# Digital_Output_C.net
KiCad netlist of a schematic drawn in EAGLE
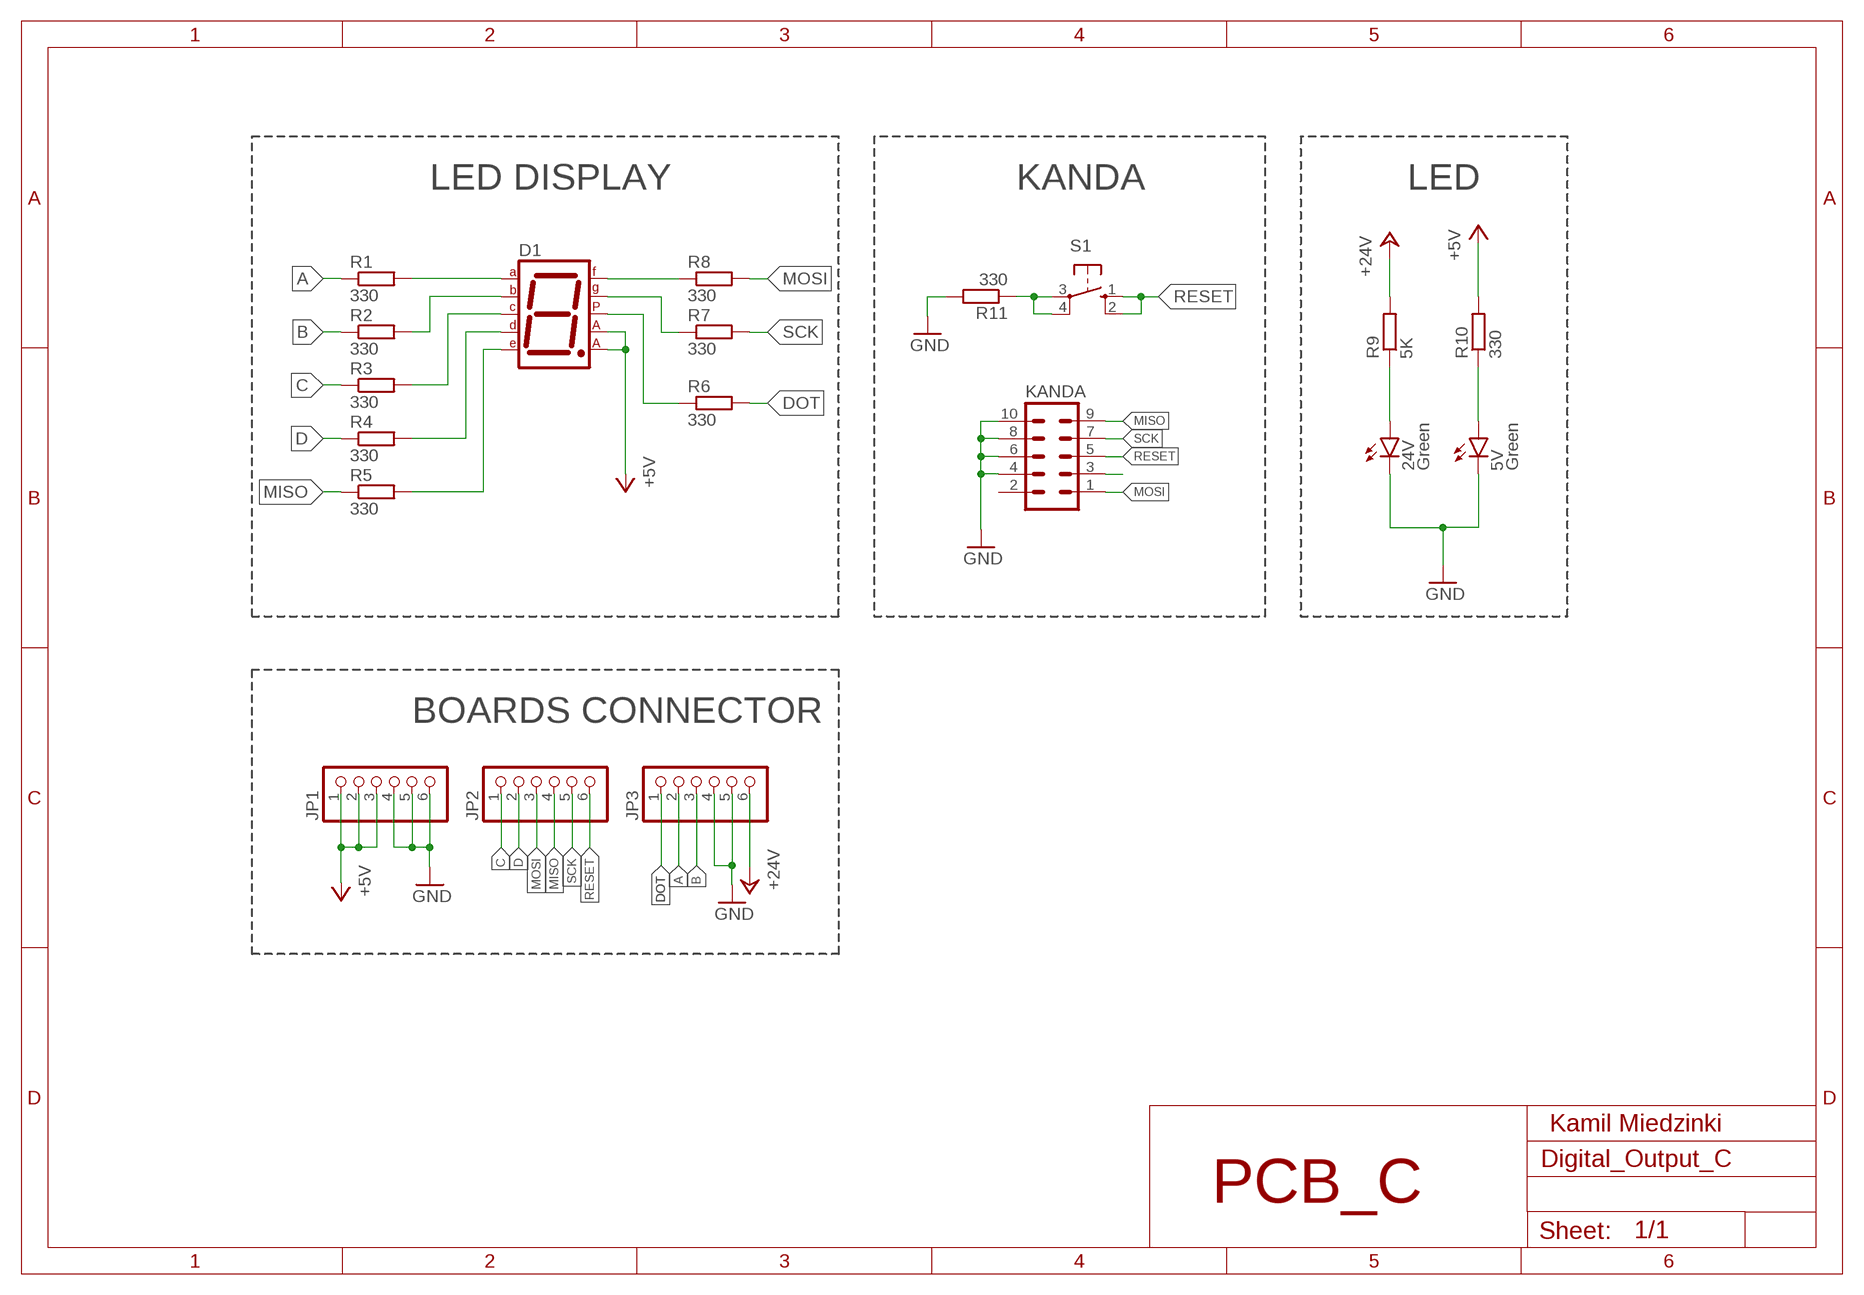
[diagram p0: schematic, sheet 1]

(export (version "E")
  (design (tool "Eeschema 10.0.6"))
  (components
    (comp (ref "5V")
      (value "Green")
      (footprint "eagle-import:LED5MM")
      (libsource (lib "eagle-import") (part "LED5MM"))
    )
    (comp (ref "24V")
      (value "Green")
      (footprint "eagle-import:LED5MM")
      (libsource (lib "eagle-import") (part "LED5MM"))
    )
    (comp (ref "D1")
      (value "7SEG-CA")
      (footprint "eagle-import:7SEG-13")
      (libsource (lib "eagle-import") (part "7SEG-CA"))
    )
    (comp (ref "JP1")
      (value "PINHD-1X6\"")
      (footprint "eagle-import:1X06H")
      (libsource (lib "eagle-import") (part "PINHD-1X6{dblquote}"))
    )
    (comp (ref "JP2")
      (value "PINHD-1X6\"")
      (footprint "eagle-import:1X06H")
      (libsource (lib "eagle-import") (part "PINHD-1X6{dblquote}"))
    )
    (comp (ref "JP3")
      (value "PINHD-1X6\"")
      (footprint "eagle-import:1X06H")
      (libsource (lib "eagle-import") (part "PINHD-1X6{dblquote}"))
    )
    (comp (ref "KANDA")
      (value "ML10")
      (footprint "eagle-import:ML10")
      (libsource (lib "eagle-import") (part "ML10"))
    )
    (comp (ref "R1")
      (value "330")
      (footprint "eagle-import:R0805")
      (libsource (lib "eagle-import") (part "R-EU_R0805"))
    )
    (comp (ref "R2")
      (value "330")
      (footprint "eagle-import:R0805")
      (libsource (lib "eagle-import") (part "R-EU_R0805"))
    )
    (comp (ref "R3")
      (value "330")
      (footprint "eagle-import:R0805")
      (libsource (lib "eagle-import") (part "R-EU_R0805"))
    )
    (comp (ref "R4")
      (value "330")
      (footprint "eagle-import:R0805")
      (libsource (lib "eagle-import") (part "R-EU_R0805"))
    )
    (comp (ref "R5")
      (value "330")
      (footprint "eagle-import:R0805")
      (libsource (lib "eagle-import") (part "R-EU_R0805"))
    )
    (comp (ref "R6")
      (value "330")
      (footprint "eagle-import:R0805")
      (libsource (lib "eagle-import") (part "R-EU_R0805"))
    )
    (comp (ref "R7")
      (value "330")
      (footprint "eagle-import:R0805")
      (libsource (lib "eagle-import") (part "R-EU_R0805"))
    )
    (comp (ref "R8")
      (value "330")
      (footprint "eagle-import:R0805")
      (libsource (lib "eagle-import") (part "R-EU_R0805"))
    )
    (comp (ref "R9")
      (value "5K")
      (footprint "eagle-import:0207_7")
      (libsource (lib "eagle-import") (part "R-EU_0207/7"))
    )
    (comp (ref "R10")
      (value "330")
      (footprint "eagle-import:0207_7")
      (libsource (lib "eagle-import") (part "R-EU_0207/7"))
    )
    (comp (ref "R11")
      (value "330")
      (footprint "eagle-import:R0805")
      (libsource (lib "eagle-import") (part "R-EU_R0805"))
    )
    (comp (ref "S1")
      (value "10-XX")
      (footprint "eagle-import:B3F-10XX")
      (fields (field (name "MPN") "B3F-1000"))
      (libsource (lib "eagle-import") (part "10-XX"))
    )
  )
  (nets
    (net (code "1") (name "+5V") (class "Default")
      (node (ref "D1") (pin "3") (pinfunction "CA1_3") (pintype "passive"))
      (node (ref "D1") (pin "8") (pinfunction "CA2_8") (pintype "passive"))
      (node (ref "JP1") (pin "1") (pinfunction "1_1") (pintype "passive"))
      (node (ref "JP1") (pin "2") (pinfunction "2_2") (pintype "passive"))
      (node (ref "JP1") (pin "3") (pinfunction "3_3") (pintype "passive"))
      (node (ref "R10") (pin "2") (pinfunction "2_2") (pintype "passive"))
    )
    (net (code "2") (name "+24V") (class "Default")
      (node (ref "JP3") (pin "6") (pinfunction "6_6") (pintype "passive"))
      (node (ref "R9") (pin "2") (pinfunction "2_2") (pintype "passive"))
    )
    (net (code "3") (name "A") (class "Default")
      (node (ref "JP3") (pin "2") (pinfunction "2_2") (pintype "passive"))
      (node (ref "R1") (pin "1") (pinfunction "1_1") (pintype "passive"))
    )
    (net (code "4") (name "B") (class "Default")
      (node (ref "JP3") (pin "3") (pinfunction "3_3") (pintype "passive"))
      (node (ref "R2") (pin "1") (pinfunction "1_1") (pintype "passive"))
    )
    (net (code "5") (name "C") (class "Default")
      (node (ref "JP2") (pin "1") (pinfunction "1_1") (pintype "passive"))
      (node (ref "R3") (pin "1") (pinfunction "1_1") (pintype "passive"))
    )
    (net (code "6") (name "D") (class "Default")
      (node (ref "JP2") (pin "2") (pinfunction "2_2") (pintype "passive"))
      (node (ref "R4") (pin "1") (pinfunction "1_1") (pintype "passive"))
    )
    (net (code "7") (name "DOT") (class "Default")
      (node (ref "JP3") (pin "1") (pinfunction "1_1") (pintype "passive"))
      (node (ref "R6") (pin "2") (pinfunction "2_2") (pintype "passive"))
    )
    (net (code "8") (name "GND") (class "Default")
      (node (ref "24V") (pin "K") (pinfunction "C_K") (pintype "passive"))
      (node (ref "5V") (pin "K") (pinfunction "C_K") (pintype "passive"))
      (node (ref "JP1") (pin "4") (pinfunction "4_4") (pintype "passive"))
      (node (ref "JP1") (pin "5") (pinfunction "5_5") (pintype "passive"))
      (node (ref "JP1") (pin "6") (pinfunction "6_6") (pintype "passive"))
      (node (ref "JP3") (pin "4") (pinfunction "4_4") (pintype "passive"))
      (node (ref "JP3") (pin "5") (pinfunction "5_5") (pintype "passive"))
      (node (ref "KANDA") (pin "10") (pinfunction "10_10") (pintype "passive"))
      (node (ref "KANDA") (pin "4") (pinfunction "4_4") (pintype "passive"))
      (node (ref "KANDA") (pin "6") (pinfunction "6_6") (pintype "passive"))
      (node (ref "KANDA") (pin "8") (pinfunction "8_8") (pintype "passive"))
      (node (ref "R11") (pin "2") (pinfunction "2_2") (pintype "passive"))
    )
    (net (code "9") (name "MISO") (class "Default")
      (node (ref "JP2") (pin "4") (pinfunction "4_4") (pintype "passive"))
      (node (ref "KANDA") (pin "9") (pinfunction "9_9") (pintype "passive"))
      (node (ref "R5") (pin "1") (pinfunction "1_1") (pintype "passive"))
    )
    (net (code "10") (name "MOSI") (class "Default")
      (node (ref "JP2") (pin "3") (pinfunction "3_3") (pintype "passive"))
      (node (ref "KANDA") (pin "1") (pinfunction "1_1") (pintype "passive"))
      (node (ref "R8") (pin "2") (pinfunction "2_2") (pintype "passive"))
    )
    (net (code "11") (name "Net-(5V-PadA)") (class "Default")
      (node (ref "5V") (pin "A") (pinfunction "A_A") (pintype "passive"))
      (node (ref "R10") (pin "1") (pinfunction "1_1") (pintype "passive"))
    )
    (net (code "12") (name "Net-(24V-PadA)") (class "Default")
      (node (ref "24V") (pin "A") (pinfunction "A_A") (pintype "passive"))
      (node (ref "R9") (pin "1") (pinfunction "1_1") (pintype "passive"))
    )
    (net (code "13") (name "Net-(D1-A)") (class "Default")
      (node (ref "D1") (pin "7") (pinfunction "A_7") (pintype "passive"))
      (node (ref "R1") (pin "2") (pinfunction "2_2") (pintype "passive"))
    )
    (net (code "14") (name "Net-(D1-B)") (class "Default")
      (node (ref "D1") (pin "6") (pinfunction "B_6") (pintype "passive"))
      (node (ref "R2") (pin "2") (pinfunction "2_2") (pintype "passive"))
    )
    (net (code "15") (name "Net-(D1-C)") (class "Default")
      (node (ref "D1") (pin "4") (pinfunction "C_4") (pintype "passive"))
      (node (ref "R3") (pin "2") (pinfunction "2_2") (pintype "passive"))
    )
    (net (code "16") (name "Net-(D1-D)") (class "Default")
      (node (ref "D1") (pin "2") (pinfunction "D_2") (pintype "passive"))
      (node (ref "R4") (pin "2") (pinfunction "2_2") (pintype "passive"))
    )
    (net (code "17") (name "Net-(D1-DP)") (class "Default")
      (node (ref "D1") (pin "5") (pinfunction "DP_5") (pintype "passive"))
      (node (ref "R6") (pin "1") (pinfunction "1_1") (pintype "passive"))
    )
    (net (code "18") (name "Net-(D1-E)") (class "Default")
      (node (ref "D1") (pin "1") (pinfunction "E_1") (pintype "passive"))
      (node (ref "R5") (pin "2") (pinfunction "2_2") (pintype "passive"))
    )
    (net (code "19") (name "Net-(D1-F)") (class "Default")
      (node (ref "D1") (pin "9") (pinfunction "F_9") (pintype "passive"))
      (node (ref "R8") (pin "1") (pinfunction "1_1") (pintype "passive"))
    )
    (net (code "20") (name "Net-(D1-G)") (class "Default")
      (node (ref "D1") (pin "10") (pinfunction "G_10") (pintype "passive"))
      (node (ref "R7") (pin "1") (pinfunction "1_1") (pintype "passive"))
    )
    (net (code "21") (name "Net-(S1-P)") (class "Default")
      (node (ref "R11") (pin "1") (pinfunction "1_1") (pintype "passive"))
      (node (ref "S1") (pin "3") (pinfunction "P_3") (pintype "passive"))
      (node (ref "S1") (pin "4") (pinfunction "P1_4") (pintype "passive"))
    )
    (net (code "22") (name "RESET") (class "Default")
      (node (ref "JP2") (pin "6") (pinfunction "6_6") (pintype "passive"))
      (node (ref "KANDA") (pin "5") (pinfunction "5_5") (pintype "passive"))
      (node (ref "S1") (pin "1") (pinfunction "S_1") (pintype "passive"))
      (node (ref "S1") (pin "2") (pinfunction "S1_2") (pintype "passive"))
    )
    (net (code "23") (name "SCK") (class "Default")
      (node (ref "JP2") (pin "5") (pinfunction "5_5") (pintype "passive"))
      (node (ref "KANDA") (pin "7") (pinfunction "7_7") (pintype "passive"))
      (node (ref "R7") (pin "2") (pinfunction "2_2") (pintype "passive"))
    )
    (net (code "24") (name "unconnected-(KANDA-Pad2)") (class "Default")
      (node (ref "KANDA") (pin "2") (pinfunction "2_2") (pintype "passive"))
    )
    (net (code "25") (name "unconnected-(KANDA-Pad3)") (class "Default")
      (node (ref "KANDA") (pin "3") (pinfunction "3_3") (pintype "passive"))
    )
  )
)
